# PWR_TPS62821-2-3.net
KiCad netlist of a schematic drawn in Altium Designer
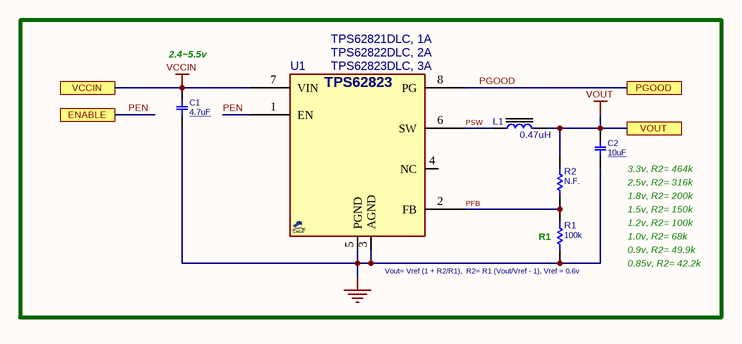
[diagram p0: PWR_TPS62821-2-3.SchDoc]

(export (version "E")
  (design (tool "Eeschema 10.0.6"))
  (components
    (comp (ref "C1")
      (value "4.7uF")
      (footprint "C0402A")
      (description "CAP, MLCC")
      (fields (field (name "MANF_P#") "GRM155R61A475MEAAD"))
      (libsource (lib "passive_smd") (part "CAP_SMD_MLCC"))
    )
    (comp (ref "C2")
      (value "10uF")
      (footprint "C0402A")
      (description "CAP, MLCC")
      (fields (field (name "MANF_P#") "CL05A106MP5NUNC"))
      (libsource (lib "passive_smd") (part "CAP_SMD_MLCC"))
    )
    (comp (ref "L1")
      (value "0.47uH")
      (footprint "L0805OVER")
      (description "INDUCTOR, POWER, SMD")
      (fields (field (name "MANF_P#") "SRP0420-R68K"))
      (libsource (lib "passive_smd") (part "INDPWR_SMD"))
    )
    (comp (ref "R1")
      (value "100k")
      (footprint "R0402A")
      (description "RESISTOR, SMD")
      (libsource (lib "passive_smd") (part "RES_SMD"))
    )
    (comp (ref "R2")
      (value "N.F.")
      (footprint "R0402A")
      (description "RESISTOR, SMD")
      (libsource (lib "passive_smd") (part "RES_SMD"))
    )
    (comp (ref "U1")
      (value "TPS62823")
      (footprint "SON50_8_2015")
      (description "REG, Switching, Buck, 3A, ADJ, 2.2MHz, 2.4~5.5VIN, SON-8")
      (fields (field (name "MANF_P#") "TPS62823DLC") (field (name "MANF") "Texas Instruments"))
      (libsource (lib "pwr_switching_buck") (part "VREG_TPS62823_SON8"))
    )
  )
  (nets
    (net (code "1") (name "/PEN") (class "Default")
      (node (ref "U1") (pin "1") (pinfunction "EN_1") (pintype "passive"))
    )
    (net (code "2") (name "/PFB") (class "Default")
      (node (ref "R1") (pin "2") (pinfunction "2_2") (pintype "passive"))
      (node (ref "R2") (pin "1") (pinfunction "1_1") (pintype "passive"))
      (node (ref "U1") (pin "2") (pinfunction "FB_2") (pintype "passive"))
    )
    (net (code "3") (name "/PGOOD") (class "Default")
      (node (ref "U1") (pin "8") (pinfunction "PG_8") (pintype "passive"))
    )
    (net (code "4") (name "/PSW") (class "Default")
      (node (ref "L1") (pin "1") (pinfunction "1_1") (pintype "passive"))
      (node (ref "U1") (pin "6") (pinfunction "SW_6") (pintype "power_in"))
    )
    (net (code "5") (name "GND") (class "Default")
      (node (ref "C1") (pin "2") (pinfunction "2_2") (pintype "passive"))
      (node (ref "C2") (pin "2") (pinfunction "2_2") (pintype "passive"))
      (node (ref "R1") (pin "1") (pinfunction "1_1") (pintype "passive"))
      (node (ref "U1") (pin "3") (pinfunction "AGND_3") (pintype "passive"))
      (node (ref "U1") (pin "5") (pinfunction "PGND_5") (pintype "passive"))
    )
    (net (code "6") (name "VCCIN") (class "Default")
      (node (ref "C1") (pin "1") (pinfunction "1_1") (pintype "passive"))
      (node (ref "U1") (pin "7") (pinfunction "VIN_7") (pintype "power_in"))
    )
    (net (code "7") (name "VOUT") (class "Default")
      (node (ref "C2") (pin "1") (pinfunction "1_1") (pintype "passive"))
      (node (ref "L1") (pin "2") (pinfunction "2_2") (pintype "passive"))
      (node (ref "R2") (pin "2") (pinfunction "2_2") (pintype "passive"))
    )
    (net (code "8") (name "unconnected-(U1-NC-Pad4)") (class "Default")
      (node (ref "U1") (pin "4") (pinfunction "NC_4") (pintype "passive"))
    )
  )
)
